# RTI-RoR-wire.net
KiCad netlist of a schematic drawn in EAGLE
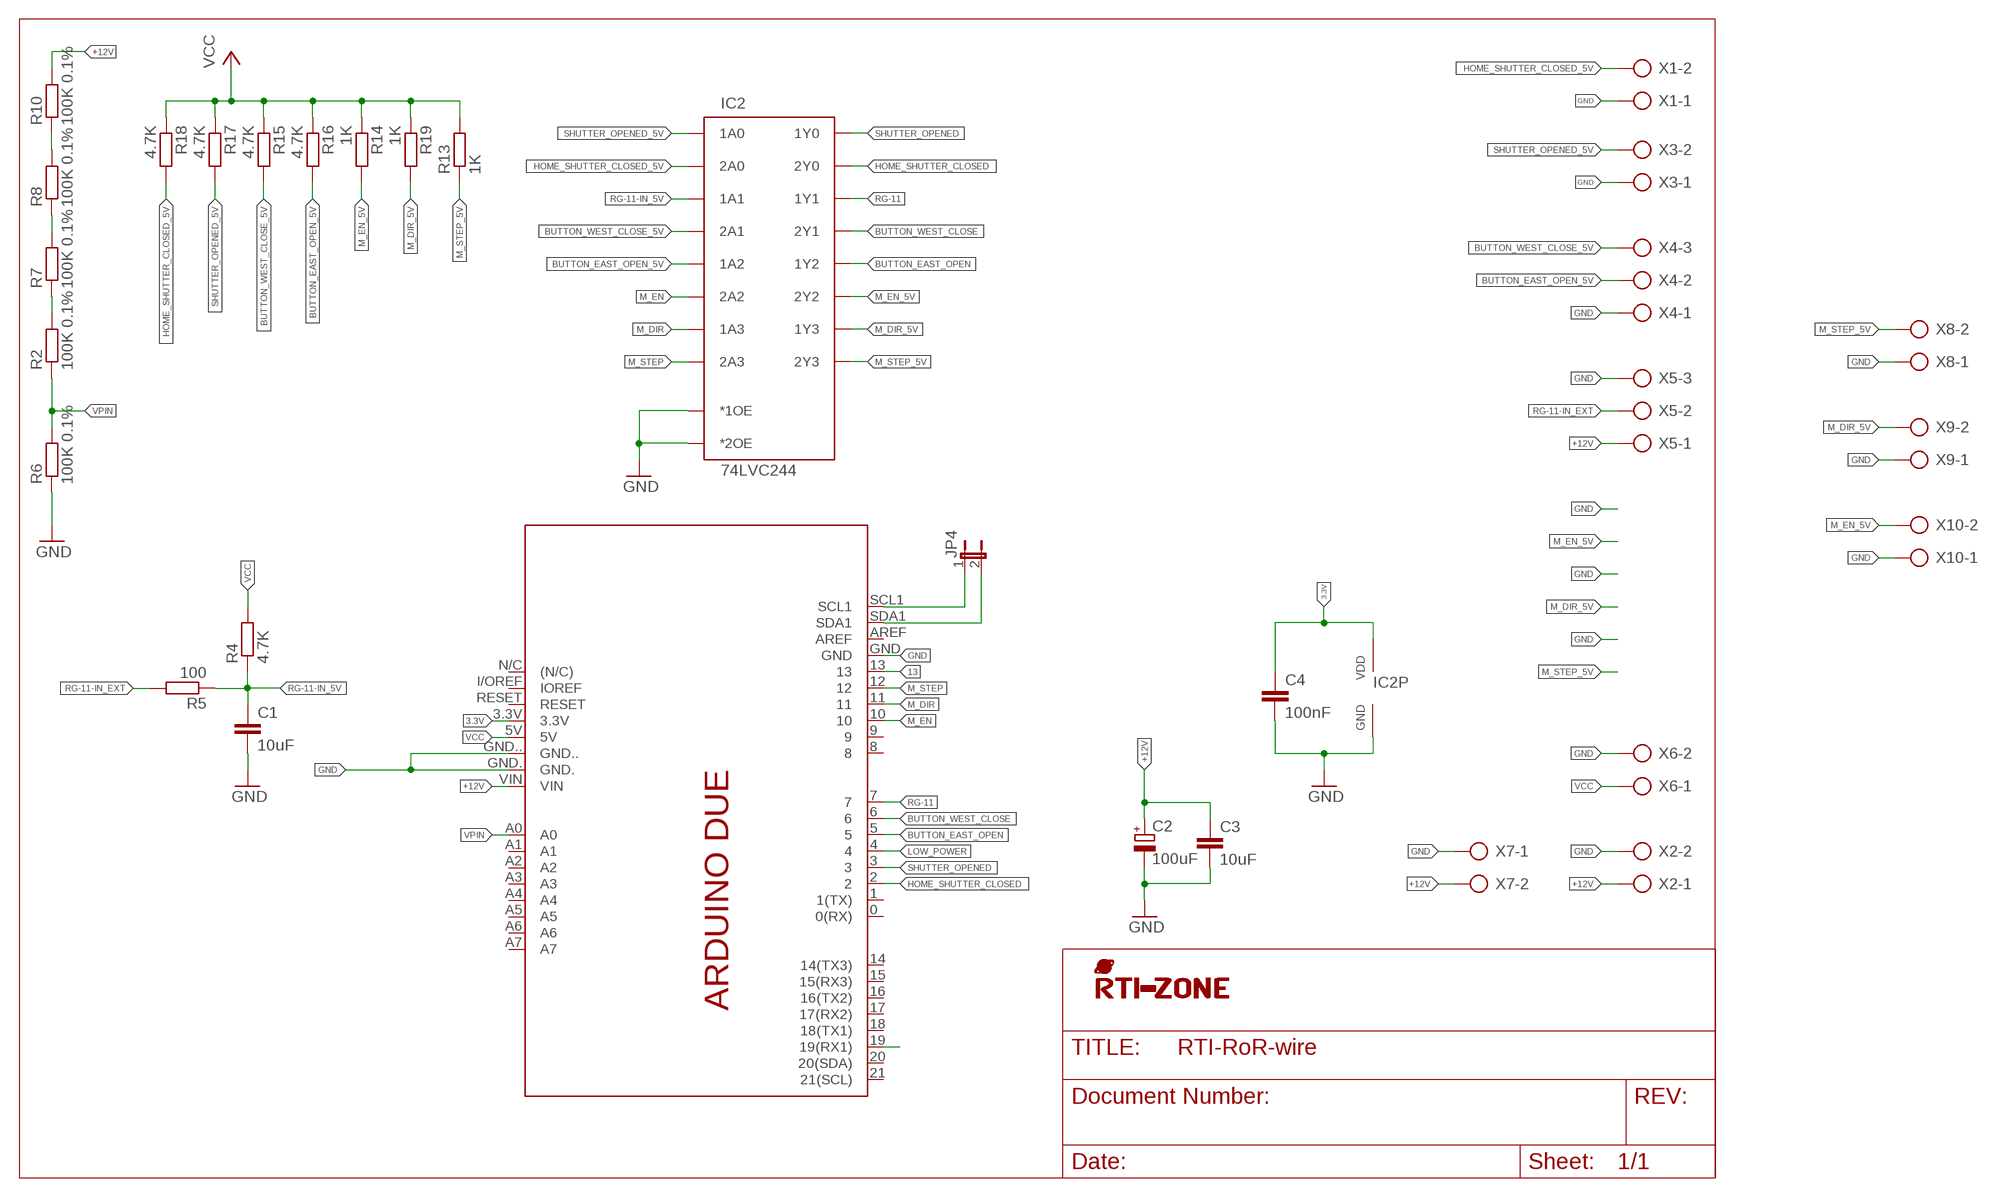
[diagram p0: schematic, sheet 1]

(export (version "E")
  (design (tool "Eeschema 10.0.6"))
  (components
    (comp (ref "C1")
      (value "10uF")
      (footprint "eagle-import:C0805")
      (libsource (lib "eagle-import") (part "C-EU'0805'"))
    )
    (comp (ref "C2")
      (value "100uF")
      (footprint "eagle-import:UD-10X10_NICHICON")
      (libsource (lib "eagle-import") (part "CPOL-EU"))
    )
    (comp (ref "C3")
      (value "10uF")
      (footprint "eagle-import:C0805")
      (libsource (lib "eagle-import") (part "C-EU'0805'"))
    )
    (comp (ref "C4")
      (value "100nF")
      (footprint "eagle-import:C0805")
      (libsource (lib "eagle-import") (part "C-EU'0805'"))
    )
    (comp (ref "IC2")
      (value "74LVC244")
      (footprint "eagle-import:TSSOP20")
      (libsource (lib "eagle-import") (part "74244LVC"))
    )
    (comp (ref "JP4")
      (value "JP1E")
      (footprint "eagle-import:JP1")
      (libsource (lib "eagle-import") (part "JP1E"))
    )
    (comp (ref "PCB1")
      (value "ARDUINO_DUE_SHIELD_SHORT")
      (footprint "eagle-import:ARDUINO_DUE_SHIELD_SHORT")
      (libsource (lib "eagle-import") (part "ARDUINO_DUE_SHIELD_SHORT"))
    )
    (comp (ref "R2")
      (value "100K 0.1%")
      (footprint "eagle-import:R0805")
      (libsource (lib "eagle-import") (part "R-EU'0805'"))
    )
    (comp (ref "R4")
      (value "4.7K")
      (footprint "eagle-import:R0805")
      (libsource (lib "eagle-import") (part "R-EU'0805'"))
    )
    (comp (ref "R5")
      (value "100")
      (footprint "eagle-import:R0805")
      (libsource (lib "eagle-import") (part "R-EU'0805'"))
    )
    (comp (ref "R6")
      (value "100K 0.1%")
      (footprint "eagle-import:R0805")
      (libsource (lib "eagle-import") (part "R-EU'0805'"))
    )
    (comp (ref "R7")
      (value "100K 0.1%")
      (footprint "eagle-import:R0805")
      (libsource (lib "eagle-import") (part "R-EU'0805'"))
    )
    (comp (ref "R8")
      (value "100K 0.1%")
      (footprint "eagle-import:R0805")
      (libsource (lib "eagle-import") (part "R-EU'0805'"))
    )
    (comp (ref "R10")
      (value "100K 0.1%")
      (footprint "eagle-import:R0805")
      (libsource (lib "eagle-import") (part "R-EU'0805'"))
    )
    (comp (ref "R13")
      (value "1K")
      (footprint "eagle-import:R0805")
      (libsource (lib "eagle-import") (part "R-EU'0805'"))
    )
    (comp (ref "R14")
      (value "1K")
      (footprint "eagle-import:R0805")
      (libsource (lib "eagle-import") (part "R-EU'0805'"))
    )
    (comp (ref "R15")
      (value "4.7K")
      (footprint "eagle-import:R0805")
      (libsource (lib "eagle-import") (part "R-EU'0805'"))
    )
    (comp (ref "R16")
      (value "4.7K")
      (footprint "eagle-import:R0805")
      (libsource (lib "eagle-import") (part "R-EU'0805'"))
    )
    (comp (ref "R17")
      (value "4.7K")
      (footprint "eagle-import:R0805")
      (libsource (lib "eagle-import") (part "R-EU'0805'"))
    )
    (comp (ref "R18")
      (value "4.7K")
      (footprint "eagle-import:R0805")
      (libsource (lib "eagle-import") (part "R-EU'0805'"))
    )
    (comp (ref "R19")
      (value "1K")
      (footprint "eagle-import:R0805")
      (libsource (lib "eagle-import") (part "R-EU'0805'"))
    )
    (comp (ref "U$4")
      (value "RTI-LOGO_BIG")
      (footprint "eagle-import:LOGO_BIG")
      (libsource (lib "eagle-import") (part "RTI-LOGO_BIG"))
    )
    (comp (ref "X1")
      (value "AK500/2")
      (footprint "eagle-import:AK500_2")
      (libsource (lib "eagle-import") (part "AK500/2"))
    )
    (comp (ref "X2")
      (value "AK500/2")
      (footprint "eagle-import:AK500_2")
      (libsource (lib "eagle-import") (part "AK500/2"))
    )
    (comp (ref "X3")
      (value "AK500/2")
      (footprint "eagle-import:AK500_2")
      (libsource (lib "eagle-import") (part "AK500/2"))
    )
    (comp (ref "X4")
      (value "AK500/3")
      (footprint "eagle-import:AK500_3")
      (libsource (lib "eagle-import") (part "AK500/3"))
    )
    (comp (ref "X5")
      (value "AK500/3")
      (footprint "eagle-import:AK500_3")
      (libsource (lib "eagle-import") (part "AK500/3"))
    )
    (comp (ref "X6")
      (value "AK500/2")
      (footprint "eagle-import:AK500_2")
      (libsource (lib "eagle-import") (part "AK500/2"))
    )
    (comp (ref "X7")
      (value "AK500/2")
      (footprint "eagle-import:AK500_2")
      (libsource (lib "eagle-import") (part "AK500/2"))
    )
    (comp (ref "X8")
      (value "AK500/2")
      (footprint "eagle-import:AK500_2")
      (libsource (lib "eagle-import") (part "AK500/2"))
    )
    (comp (ref "X9")
      (value "AK500/2")
      (footprint "eagle-import:AK500_2")
      (libsource (lib "eagle-import") (part "AK500/2"))
    )
    (comp (ref "X10")
      (value "AK500/2")
      (footprint "eagle-import:AK500_2")
      (libsource (lib "eagle-import") (part "AK500/2"))
    )
  )
  (nets
    (net (code "1") (name "+12V") (class "Default")
      (node (ref "C2") (pin "+") (pinfunction "+_+") (pintype "passive"))
      (node (ref "C3") (pin "1") (pinfunction "1_1") (pintype "passive"))
      (node (ref "PCB1") (pin "VIN") (pinfunction "VIN_VIN") (pintype "bidirectional"))
      (node (ref "R10") (pin "2") (pinfunction "2_2") (pintype "passive"))
      (node (ref "X2") (pin "1") (pinfunction "KL_1") (pintype "passive"))
      (node (ref "X5") (pin "1") (pinfunction "KL_1") (pintype "passive"))
      (node (ref "X7") (pin "2") (pinfunction "KL_2") (pintype "passive"))
    )
    (net (code "2") (name "3.3V") (class "Default")
      (node (ref "C4") (pin "1") (pinfunction "1_1") (pintype "passive"))
      (node (ref "IC2") (pin "P$20") (pinfunction "VDD_P$20") (pintype "power_in"))
      (node (ref "PCB1") (pin "3.3V") (pinfunction "3.3V_3.3V") (pintype "bidirectional"))
    )
    (net (code "3") (name "13") (class "Default")
      (node (ref "PCB1") (pin "13") (pinfunction "13_13") (pintype "bidirectional"))
    )
    (net (code "4") (name "BUTTON_EAST_OPEN") (class "Default")
      (node (ref "IC2") (pin "P$14") (pinfunction "1Y2_P$14") (pintype "output"))
      (node (ref "PCB1") (pin "5") (pinfunction "5_5") (pintype "bidirectional"))
    )
    (net (code "5") (name "BUTTON_EAST_OPEN_5V") (class "Default")
      (node (ref "IC2") (pin "P$6") (pinfunction "1A2_P$6") (pintype "input"))
      (node (ref "R16") (pin "2") (pinfunction "2_2") (pintype "passive"))
      (node (ref "X4") (pin "2") (pinfunction "KL_2") (pintype "passive"))
    )
    (net (code "6") (name "BUTTON_WEST_CLOSE") (class "Default")
      (node (ref "IC2") (pin "P$5") (pinfunction "2Y1_P$5") (pintype "output"))
      (node (ref "PCB1") (pin "6") (pinfunction "6_6") (pintype "bidirectional"))
    )
    (net (code "7") (name "BUTTON_WEST_CLOSE_5V") (class "Default")
      (node (ref "IC2") (pin "P$15") (pinfunction "2A1_P$15") (pintype "input"))
      (node (ref "R15") (pin "2") (pinfunction "2_2") (pintype "passive"))
      (node (ref "X4") (pin "3") (pinfunction "KL_3") (pintype "passive"))
    )
    (net (code "8") (name "GND") (class "Default")
      (node (ref "C1") (pin "2") (pinfunction "2_2") (pintype "passive"))
      (node (ref "C2") (pin "-") (pinfunction "-_-") (pintype "passive"))
      (node (ref "C3") (pin "2") (pinfunction "2_2") (pintype "passive"))
      (node (ref "C4") (pin "2") (pinfunction "2_2") (pintype "passive"))
      (node (ref "IC2") (pin "P$1") (pinfunction "*1OE_P$1") (pintype "input"))
      (node (ref "IC2") (pin "P$10") (pinfunction "GND_P$10") (pintype "power_in"))
      (node (ref "IC2") (pin "P$19") (pinfunction "*2OE_P$19") (pintype "input"))
      (node (ref "PCB1") (pin "GND") (pinfunction "GND_GND") (pintype "bidirectional"))
      (node (ref "PCB1") (pin "GND.") (pinfunction "GND._GND.") (pintype "bidirectional"))
      (node (ref "PCB1") (pin "GND..") (pinfunction "GND.._GND..") (pintype "bidirectional"))
      (node (ref "R6") (pin "1") (pinfunction "1_1") (pintype "passive"))
      (node (ref "X1") (pin "1") (pinfunction "KL_1") (pintype "passive"))
      (node (ref "X10") (pin "1") (pinfunction "KL_1") (pintype "passive"))
      (node (ref "X2") (pin "2") (pinfunction "KL_2") (pintype "passive"))
      (node (ref "X3") (pin "1") (pinfunction "KL_1") (pintype "passive"))
      (node (ref "X4") (pin "1") (pinfunction "KL_1") (pintype "passive"))
      (node (ref "X5") (pin "3") (pinfunction "KL_3") (pintype "passive"))
      (node (ref "X6") (pin "2") (pinfunction "KL_2") (pintype "passive"))
      (node (ref "X7") (pin "1") (pinfunction "KL_1") (pintype "passive"))
      (node (ref "X8") (pin "1") (pinfunction "KL_1") (pintype "passive"))
      (node (ref "X9") (pin "1") (pinfunction "KL_1") (pintype "passive"))
    )
    (net (code "9") (name "HOME_SHUTTER_CLOSED") (class "Default")
      (node (ref "IC2") (pin "P$3") (pinfunction "2Y0_P$3") (pintype "output"))
      (node (ref "PCB1") (pin "2") (pinfunction "2_2") (pintype "bidirectional"))
    )
    (net (code "10") (name "HOME_SHUTTER_CLOSED_5V") (class "Default")
      (node (ref "IC2") (pin "P$17") (pinfunction "2A0_P$17") (pintype "input"))
      (node (ref "R18") (pin "2") (pinfunction "2_2") (pintype "passive"))
      (node (ref "X1") (pin "2") (pinfunction "KL_2") (pintype "passive"))
    )
    (net (code "11") (name "LOW_POWER") (class "Default")
      (node (ref "PCB1") (pin "4") (pinfunction "4_4") (pintype "bidirectional"))
    )
    (net (code "12") (name "M_DIR") (class "Default")
      (node (ref "IC2") (pin "P$8") (pinfunction "1A3_P$8") (pintype "input"))
      (node (ref "PCB1") (pin "11") (pinfunction "11_11") (pintype "bidirectional"))
    )
    (net (code "13") (name "M_DIR_5V") (class "Default")
      (node (ref "IC2") (pin "P$12") (pinfunction "1Y3_P$12") (pintype "output"))
      (node (ref "R19") (pin "2") (pinfunction "2_2") (pintype "passive"))
      (node (ref "X9") (pin "2") (pinfunction "KL_2") (pintype "passive"))
    )
    (net (code "14") (name "M_EN") (class "Default")
      (node (ref "IC2") (pin "P$13") (pinfunction "2A2_P$13") (pintype "input"))
      (node (ref "PCB1") (pin "10") (pinfunction "10_10") (pintype "bidirectional"))
    )
    (net (code "15") (name "M_EN_5V") (class "Default")
      (node (ref "IC2") (pin "P$7") (pinfunction "2Y2_P$7") (pintype "output"))
      (node (ref "R14") (pin "2") (pinfunction "2_2") (pintype "passive"))
      (node (ref "X10") (pin "2") (pinfunction "KL_2") (pintype "passive"))
    )
    (net (code "16") (name "M_STEP") (class "Default")
      (node (ref "IC2") (pin "P$11") (pinfunction "2A3_P$11") (pintype "input"))
      (node (ref "PCB1") (pin "12") (pinfunction "12_12") (pintype "bidirectional"))
    )
    (net (code "17") (name "M_STEP_5V") (class "Default")
      (node (ref "IC2") (pin "P$9") (pinfunction "2Y3_P$9") (pintype "output"))
      (node (ref "R13") (pin "1") (pinfunction "1_1") (pintype "passive"))
      (node (ref "X8") (pin "2") (pinfunction "KL_2") (pintype "passive"))
    )
    (net (code "18") (name "Net-(JP4-Pad1)") (class "Default")
      (node (ref "JP4") (pin "1") (pinfunction "1_1") (pintype "passive"))
      (node (ref "PCB1") (pin "SCL1") (pinfunction "SCL1_SCL1") (pintype "bidirectional"))
    )
    (net (code "19") (name "Net-(JP4-Pad2)") (class "Default")
      (node (ref "JP4") (pin "2") (pinfunction "2_2") (pintype "passive"))
      (node (ref "PCB1") (pin "SDA1") (pinfunction "SDA1_SDA1") (pintype "bidirectional"))
    )
    (net (code "20") (name "Net-(R2-Pad2)") (class "Default")
      (node (ref "R2") (pin "2") (pinfunction "2_2") (pintype "passive"))
      (node (ref "R7") (pin "1") (pinfunction "1_1") (pintype "passive"))
    )
    (net (code "21") (name "Net-(R7-Pad2)") (class "Default")
      (node (ref "R7") (pin "2") (pinfunction "2_2") (pintype "passive"))
      (node (ref "R8") (pin "1") (pinfunction "1_1") (pintype "passive"))
    )
    (net (code "22") (name "Net-(R10-Pad1)") (class "Default")
      (node (ref "R10") (pin "1") (pinfunction "1_1") (pintype "passive"))
      (node (ref "R8") (pin "2") (pinfunction "2_2") (pintype "passive"))
    )
    (net (code "23") (name "RG-11") (class "Default")
      (node (ref "IC2") (pin "P$16") (pinfunction "1Y1_P$16") (pintype "output"))
      (node (ref "PCB1") (pin "7") (pinfunction "7_7") (pintype "bidirectional"))
    )
    (net (code "24") (name "RG-11-IN_5V") (class "Default")
      (node (ref "C1") (pin "1") (pinfunction "1_1") (pintype "passive"))
      (node (ref "IC2") (pin "P$4") (pinfunction "1A1_P$4") (pintype "input"))
      (node (ref "R4") (pin "1") (pinfunction "1_1") (pintype "passive"))
      (node (ref "R5") (pin "1") (pinfunction "1_1") (pintype "passive"))
    )
    (net (code "25") (name "RG-11-IN_EXT") (class "Default")
      (node (ref "R5") (pin "2") (pinfunction "2_2") (pintype "passive"))
      (node (ref "X5") (pin "2") (pinfunction "KL_2") (pintype "passive"))
    )
    (net (code "26") (name "SHUTTER_OPENED") (class "Default")
      (node (ref "IC2") (pin "P$18") (pinfunction "1Y0_P$18") (pintype "output"))
      (node (ref "PCB1") (pin "3") (pinfunction "3_3") (pintype "bidirectional"))
    )
    (net (code "27") (name "SHUTTER_OPENED_5V") (class "Default")
      (node (ref "IC2") (pin "P$2") (pinfunction "1A0_P$2") (pintype "input"))
      (node (ref "R17") (pin "2") (pinfunction "2_2") (pintype "passive"))
      (node (ref "X3") (pin "2") (pinfunction "KL_2") (pintype "passive"))
    )
    (net (code "28") (name "VCC") (class "Default")
      (node (ref "PCB1") (pin "5V") (pinfunction "5V_5V") (pintype "bidirectional"))
      (node (ref "R13") (pin "2") (pinfunction "2_2") (pintype "passive"))
      (node (ref "R14") (pin "1") (pinfunction "1_1") (pintype "passive"))
      (node (ref "R15") (pin "1") (pinfunction "1_1") (pintype "passive"))
      (node (ref "R16") (pin "1") (pinfunction "1_1") (pintype "passive"))
      (node (ref "R17") (pin "1") (pinfunction "1_1") (pintype "passive"))
      (node (ref "R18") (pin "1") (pinfunction "1_1") (pintype "passive"))
      (node (ref "R19") (pin "1") (pinfunction "1_1") (pintype "passive"))
      (node (ref "R4") (pin "2") (pinfunction "2_2") (pintype "passive"))
      (node (ref "X6") (pin "1") (pinfunction "KL_1") (pintype "passive"))
    )
    (net (code "29") (name "VPIN") (class "Default")
      (node (ref "PCB1") (pin "A0") (pinfunction "A0_A0") (pintype "bidirectional"))
      (node (ref "R2") (pin "1") (pinfunction "1_1") (pintype "passive"))
      (node (ref "R6") (pin "2") (pinfunction "2_2") (pintype "passive"))
    )
    (net (code "30") (name "unconnected-(PCB1-(N{slash}C)-PadN{slash}C)") (class "Default")
      (node (ref "PCB1") (pin "N/C") (pinfunction "(N/C)_N/C") (pintype "bidirectional"))
    )
    (net (code "31") (name "unconnected-(PCB1-0(RX)-Pad0)") (class "Default")
      (node (ref "PCB1") (pin "0") (pinfunction "0(RX)_0") (pintype "bidirectional"))
    )
    (net (code "32") (name "unconnected-(PCB1-1(TX)-Pad1)") (class "Default")
      (node (ref "PCB1") (pin "1") (pinfunction "1(TX)_1") (pintype "bidirectional"))
    )
    (net (code "33") (name "unconnected-(PCB1-14(TX3)-Pad14)") (class "Default")
      (node (ref "PCB1") (pin "14") (pinfunction "14(TX3)_14") (pintype "bidirectional"))
    )
    (net (code "34") (name "unconnected-(PCB1-15(RX3)-Pad15)") (class "Default")
      (node (ref "PCB1") (pin "15") (pinfunction "15(RX3)_15") (pintype "bidirectional"))
    )
    (net (code "35") (name "unconnected-(PCB1-16(TX2)-Pad16)") (class "Default")
      (node (ref "PCB1") (pin "16") (pinfunction "16(TX2)_16") (pintype "bidirectional"))
    )
    (net (code "36") (name "unconnected-(PCB1-17(RX2)-Pad17)") (class "Default")
      (node (ref "PCB1") (pin "17") (pinfunction "17(RX2)_17") (pintype "bidirectional"))
    )
    (net (code "37") (name "unconnected-(PCB1-18(TX1)-Pad18)") (class "Default")
      (node (ref "PCB1") (pin "18") (pinfunction "18(TX1)_18") (pintype "bidirectional"))
    )
    (net (code "38") (name "unconnected-(PCB1-19(RX1)-Pad19)") (class "Default")
      (node (ref "PCB1") (pin "19") (pinfunction "19(RX1)_19") (pintype "bidirectional"))
    )
    (net (code "39") (name "unconnected-(PCB1-20(SDA)-Pad20)") (class "Default")
      (node (ref "PCB1") (pin "20") (pinfunction "20(SDA)_20") (pintype "bidirectional"))
    )
    (net (code "40") (name "unconnected-(PCB1-21(SCL)-Pad21)") (class "Default")
      (node (ref "PCB1") (pin "21") (pinfunction "21(SCL)_21") (pintype "bidirectional"))
    )
    (net (code "41") (name "unconnected-(PCB1-IOREF-PadI{slash}OREF)") (class "Default")
      (node (ref "PCB1") (pin "I/OREF") (pinfunction "IOREF_I/OREF") (pintype "bidirectional"))
    )
    (net (code "42") (name "unconnected-(PCB1-Pad8)") (class "Default")
      (node (ref "PCB1") (pin "8") (pinfunction "8_8") (pintype "bidirectional"))
    )
    (net (code "43") (name "unconnected-(PCB1-Pad9)") (class "Default")
      (node (ref "PCB1") (pin "9") (pinfunction "9_9") (pintype "bidirectional"))
    )
    (net (code "44") (name "unconnected-(PCB1-PadA1)") (class "Default")
      (node (ref "PCB1") (pin "A1") (pinfunction "A1_A1") (pintype "bidirectional"))
    )
    (net (code "45") (name "unconnected-(PCB1-PadA2)") (class "Default")
      (node (ref "PCB1") (pin "A2") (pinfunction "A2_A2") (pintype "bidirectional"))
    )
    (net (code "46") (name "unconnected-(PCB1-PadA3)") (class "Default")
      (node (ref "PCB1") (pin "A3") (pinfunction "A3_A3") (pintype "bidirectional"))
    )
    (net (code "47") (name "unconnected-(PCB1-PadA4)") (class "Default")
      (node (ref "PCB1") (pin "A4") (pinfunction "A4_A4") (pintype "bidirectional"))
    )
    (net (code "48") (name "unconnected-(PCB1-PadA5)") (class "Default")
      (node (ref "PCB1") (pin "A5") (pinfunction "A5_A5") (pintype "bidirectional"))
    )
    (net (code "49") (name "unconnected-(PCB1-PadA6)") (class "Default")
      (node (ref "PCB1") (pin "A6") (pinfunction "A6_A6") (pintype "bidirectional"))
    )
    (net (code "50") (name "unconnected-(PCB1-PadA7)") (class "Default")
      (node (ref "PCB1") (pin "A7") (pinfunction "A7_A7") (pintype "bidirectional"))
    )
    (net (code "51") (name "unconnected-(PCB1-PadAREF)") (class "Default")
      (node (ref "PCB1") (pin "AREF") (pinfunction "AREF_AREF") (pintype "bidirectional"))
    )
    (net (code "52") (name "unconnected-(PCB1-PadRESET)") (class "Default")
      (node (ref "PCB1") (pin "RESET") (pinfunction "RESET_RESET") (pintype "bidirectional"))
    )
  )
)
